# OpenEEW_sensor_board_-_ethernet.net
KiCad netlist of a schematic drawn in EAGLE
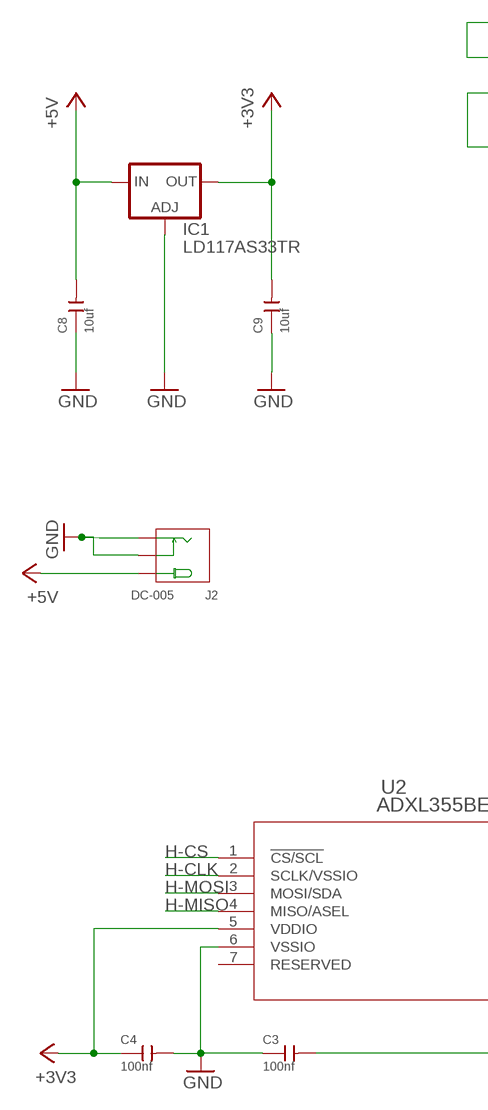
[diagram p0: schematic, sheet 1, part 1 of 2]
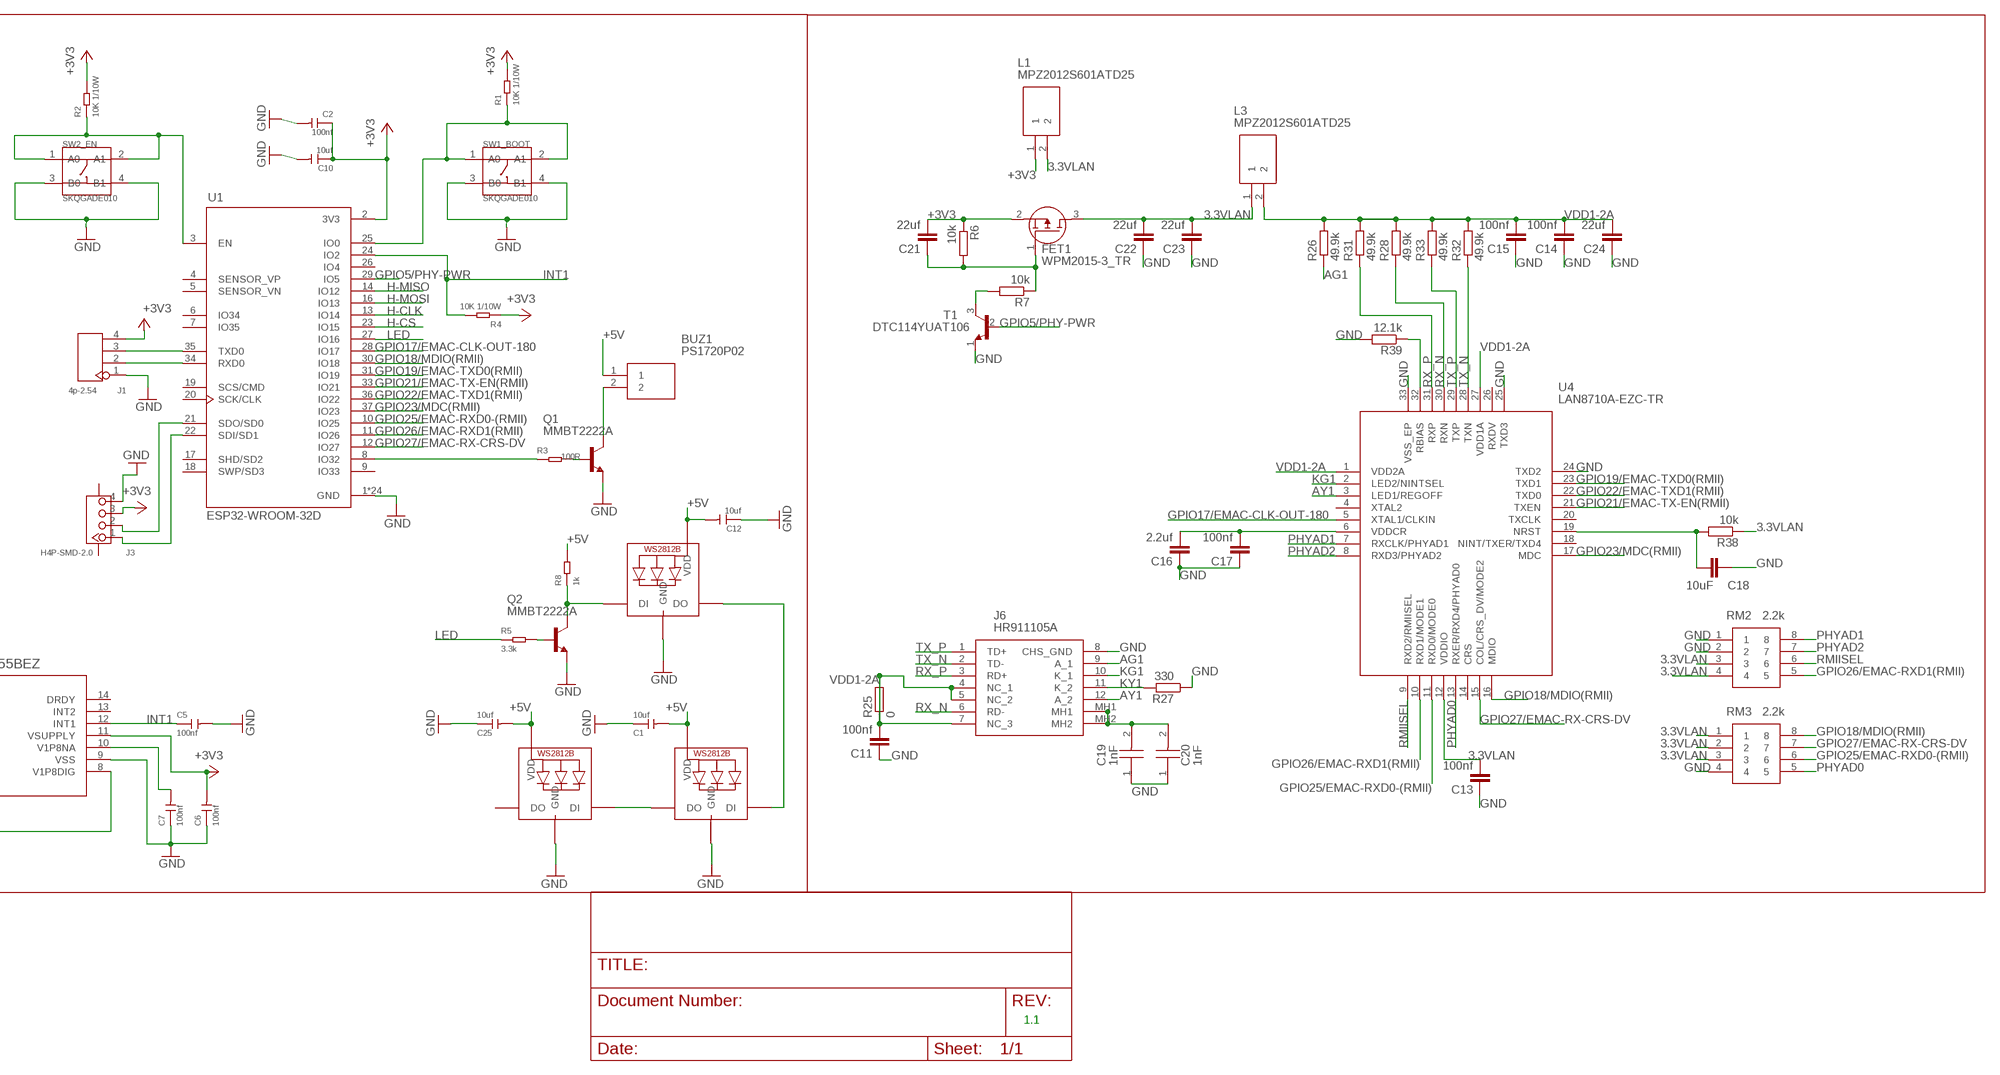
[diagram p1: schematic, sheet 1, part 2 of 2]

(export (version "E")
  (design (tool "Eeschema 10.0.6"))
  (components
    (comp (ref "BUZ1")
      (value "PS1720P02")
      (footprint "eagle-import:PS17_1")
      (fields (field (name "MOUSER_PART_NUMBER") "810-PS1720P02"))
      (libsource (lib "eagle-import") (part "PS1720P02"))
    )
    (comp (ref "C1")
      (value "10uf")
      (footprint "eagle-import:C0603")
      (fields (field (name "MPN") "CC0603KRX5R6BB106"))
      (libsource (lib "eagle-import") (part "CERAMIC-10UF-10V-10%-X5R(0603)"))
    )
    (comp (ref "C2")
      (value "100nf")
      (footprint "eagle-import:C0603")
      (fields (field (name "MPN") "CC0603KRX7R9BB104"))
      (libsource (lib "eagle-import") (part "CERAMIC-100NF-50V-10%-X7R(0603)"))
    )
    (comp (ref "C3")
      (value "100nf")
      (footprint "eagle-import:C0603")
      (fields (field (name "MPN") "CC0603KRX7R9BB104"))
      (libsource (lib "eagle-import") (part "CERAMIC-100NF-50V-10%-X7R(0603)"))
    )
    (comp (ref "C4")
      (value "100nf")
      (footprint "eagle-import:C0603")
      (fields (field (name "MPN") "CC0603KRX7R9BB104"))
      (libsource (lib "eagle-import") (part "CERAMIC-100NF-50V-10%-X7R(0603)"))
    )
    (comp (ref "C5")
      (value "100nf")
      (footprint "eagle-import:C0603")
      (fields (field (name "MPN") "CC0603KRX7R9BB104"))
      (libsource (lib "eagle-import") (part "CERAMIC-100NF-50V-10%-X7R(0603)"))
    )
    (comp (ref "C6")
      (value "100nf")
      (footprint "eagle-import:C0603")
      (fields (field (name "MPN") "CC0603KRX7R9BB104"))
      (libsource (lib "eagle-import") (part "CERAMIC-100NF-50V-10%-X7R(0603)"))
    )
    (comp (ref "C7")
      (value "100nf")
      (footprint "eagle-import:C0603")
      (fields (field (name "MPN") "CC0603KRX7R9BB104"))
      (libsource (lib "eagle-import") (part "CERAMIC-100NF-50V-10%-X7R(0603)"))
    )
    (comp (ref "C8")
      (value "10uf")
      (footprint "eagle-import:C0603")
      (fields (field (name "MPN") "CC0603KRX5R6BB106"))
      (libsource (lib "eagle-import") (part "CERAMIC-10UF-10V-10%-X5R(0603)"))
    )
    (comp (ref "C9")
      (value "10uf")
      (footprint "eagle-import:C0603")
      (fields (field (name "MPN") "CC0603KRX5R6BB106"))
      (libsource (lib "eagle-import") (part "CERAMIC-10UF-10V-10%-X5R(0603)"))
    )
    (comp (ref "C10")
      (value "10uf")
      (footprint "eagle-import:C0603")
      (fields (field (name "MPN") "CC0603KRX5R6BB106"))
      (libsource (lib "eagle-import") (part "CERAMIC-10UF-10V-10%-X5R(0603)"))
    )
    (comp (ref "C11")
      (value "100nf")
      (footprint "eagle-import:C0603")
      (libsource (lib "eagle-import") (part "C-EUC0603"))
    )
    (comp (ref "C12")
      (value "10uf")
      (footprint "eagle-import:C0603")
      (fields (field (name "MPN") "CC0603KRX5R6BB106"))
      (libsource (lib "eagle-import") (part "CERAMIC-10UF-10V-10%-X5R(0603)"))
    )
    (comp (ref "C13")
      (value "100nf")
      (footprint "eagle-import:C0603")
      (libsource (lib "eagle-import") (part "C-EUC0603"))
    )
    (comp (ref "C14")
      (value "100nf")
      (footprint "eagle-import:C0603")
      (libsource (lib "eagle-import") (part "C-EUC0603"))
    )
    (comp (ref "C15")
      (value "100nf")
      (footprint "eagle-import:C0603")
      (libsource (lib "eagle-import") (part "C-EUC0603"))
    )
    (comp (ref "C16")
      (value "2.2uf")
      (footprint "eagle-import:C0603")
      (libsource (lib "eagle-import") (part "C-EUC0603"))
    )
    (comp (ref "C17")
      (value "100nf")
      (footprint "eagle-import:C0603")
      (libsource (lib "eagle-import") (part "C-EUC0603"))
    )
    (comp (ref "C18")
      (value "10uF")
      (footprint "eagle-import:C0603")
      (libsource (lib "eagle-import") (part "C-EUC0603"))
    )
    (comp (ref "C19")
      (value "1nF")
      (footprint "eagle-import:CAPC3317X180N")
      (fields
        (field (name "ARROW_PART_NUMBER") "1206GC102KAT1A")
        (field (name "MOUSER_PART_NUMBER") "581-1206GC102K")
      )
      (libsource (lib "eagle-import") (part "1206GC102KAT1A"))
    )
    (comp (ref "C20")
      (value "1nF")
      (footprint "eagle-import:CAPC3317X180N")
      (fields
        (field (name "ARROW_PART_NUMBER") "1206GC102KAT1A")
        (field (name "MOUSER_PART_NUMBER") "581-1206GC102K")
      )
      (libsource (lib "eagle-import") (part "1206GC102KAT1A"))
    )
    (comp (ref "C21")
      (value "22uf")
      (footprint "eagle-import:C0805")
      (libsource (lib "eagle-import") (part "C-EUC0805"))
    )
    (comp (ref "C22")
      (value "22uf")
      (footprint "eagle-import:C0805")
      (libsource (lib "eagle-import") (part "C-EUC0805"))
    )
    (comp (ref "C23")
      (value "22uf")
      (footprint "eagle-import:C0805")
      (libsource (lib "eagle-import") (part "C-EUC0805"))
    )
    (comp (ref "C24")
      (value "22uf")
      (footprint "eagle-import:C0603")
      (libsource (lib "eagle-import") (part "C-EUC0603"))
    )
    (comp (ref "C25")
      (value "10uf")
      (footprint "eagle-import:C0603")
      (fields (field (name "MPN") "CC0603KRX5R6BB106"))
      (libsource (lib "eagle-import") (part "CERAMIC-10UF-10V-10%-X5R(0603)"))
    )
    (comp (ref "FET1")
      (value "WPM2015-3_TR")
      (footprint "eagle-import:SOT95P240X130-3N")
      (fields (field (name "ARROW_PART_NUMBER") "WPM2015-3/TR"))
      (libsource (lib "eagle-import") (part "WPM2015-3_TR"))
    )
    (comp (ref "IC1")
      (value "LD117AS33TR")
      (footprint "eagle-import:SOT223")
      (libsource (lib "eagle-import") (part "LD117A?S33TR"))
    )
    (comp (ref "J1")
      (value "4p-2.54")
      (footprint "eagle-import:H4-2.54")
      (fields (field (name "MPN") "P125-1104A0BS116A1"))
      (libsource (lib "eagle-import") (part "DIP-BLACK-MALE-HEADER-VERT(4P-2.54)"))
    )
    (comp (ref "J2")
      (value "DC-005")
      (footprint "eagle-import:DCJ3P-14.2X11.0X9.0MM")
      (libsource (lib "eagle-import") (part "CONN-POWER-JACK-2.1MM(DC-005)"))
    )
    (comp (ref "J3")
      (value "H4P-SMD-2.0")
      (footprint "eagle-import:HW4-SMD-2.0")
      (libsource (lib "eagle-import") (part "GROVE-CONNECTOR-SMD(4+2P-2.0)"))
    )
    (comp (ref "J6")
      (value "HR911105A")
      (footprint "eagle-import:HR911105A")
      (libsource (lib "eagle-import") (part "HR911105A"))
    )
    (comp (ref "L1")
      (value "MPZ2012S601ATD25")
      (footprint "eagle-import:BEADC2012X105N")
      (fields (field (name "MOUSER_PART_NUMBER") "810-MPZ2012S601ATD25"))
      (libsource (lib "eagle-import") (part "MPZ2012S601ATD25"))
    )
    (comp (ref "L3")
      (value "MPZ2012S601ATD25")
      (footprint "eagle-import:BEADC2012X105N")
      (fields (field (name "MOUSER_PART_NUMBER") "810-MPZ2012S601ATD25"))
      (libsource (lib "eagle-import") (part "MPZ2012S601ATD25"))
    )
    (comp (ref "LED1")
      (value "WS2812B5050")
      (footprint "eagle-import:WS2812B")
      (libsource (lib "eagle-import") (part "WS2812B5050"))
    )
    (comp (ref "LED2")
      (value "WS2812B5050")
      (footprint "eagle-import:WS2812B")
      (libsource (lib "eagle-import") (part "WS2812B5050"))
    )
    (comp (ref "LED3")
      (value "WS2812B5050")
      (footprint "eagle-import:WS2812B")
      (libsource (lib "eagle-import") (part "WS2812B5050"))
    )
    (comp (ref "Q1")
      (value "MMBT2222A")
      (footprint "eagle-import:SOT23")
      (fields (field (name "MF") "STMicroelectronics"))
      (libsource (lib "eagle-import") (part "MMBT2222A"))
    )
    (comp (ref "Q2")
      (value "MMBT2222A")
      (footprint "eagle-import:SOT23")
      (fields (field (name "MF") "STMicroelectronics"))
      (libsource (lib "eagle-import") (part "MMBT2222A"))
    )
    (comp (ref "R1")
      (value "10K 1/10W")
      (footprint "eagle-import:R0603")
      (fields (field (name "MPN") "RC0603JR-0710KL"))
      (libsource (lib "eagle-import") (part "SMD-RES-10K-5%-1/10W(0603)"))
    )
    (comp (ref "R2")
      (value "10K 1/10W")
      (footprint "eagle-import:R0603")
      (fields (field (name "MPN") "RC0603JR-0710KL"))
      (libsource (lib "eagle-import") (part "SMD-RES-10K-5%-1/10W(0603)"))
    )
    (comp (ref "R3")
      (value "100R")
      (footprint "eagle-import:R0805")
      (fields (field (name "MPN") "RC0805JR-07100RL"))
      (libsource (lib "eagle-import") (part "SMD-RES-100R-5%-1/8W(0805)"))
    )
    (comp (ref "R4")
      (value "10K 1/10W")
      (footprint "eagle-import:R0603")
      (fields (field (name "MPN") "RC0603JR-0710KL"))
      (libsource (lib "eagle-import") (part "SMD-RES-10K-5%-1/10W(0603)"))
    )
    (comp (ref "R5")
      (value "3.3k")
      (footprint "eagle-import:R0603")
      (fields (field (name "MPN") "RC0603FR-071K5L"))
      (libsource (lib "eagle-import") (part "SMD-RES-300R-1%-1/10W(0603)"))
    )
    (comp (ref "R6")
      (value "10k")
      (footprint "eagle-import:R0603")
      (libsource (lib "eagle-import") (part "R-EU_R0603"))
    )
    (comp (ref "R7")
      (value "10k")
      (footprint "eagle-import:R0603")
      (libsource (lib "eagle-import") (part "R-EU_R0603"))
    )
    (comp (ref "R8")
      (value "1k")
      (footprint "eagle-import:R0805")
      (fields (field (name "MPN") "RC0805JR-07100RL"))
      (libsource (lib "eagle-import") (part "SMD-RES-100R-5%-1/8W(0805)"))
    )
    (comp (ref "R25")
      (value "0")
      (footprint "eagle-import:R0603")
      (libsource (lib "eagle-import") (part "R-EU_R0603"))
    )
    (comp (ref "R26")
      (value "49.9k")
      (footprint "eagle-import:R0603")
      (libsource (lib "eagle-import") (part "R-EU_R0603"))
    )
    (comp (ref "R27")
      (value "330")
      (footprint "eagle-import:R0603")
      (libsource (lib "eagle-import") (part "R-EU_R0603"))
    )
    (comp (ref "R28")
      (value "49.9k")
      (footprint "eagle-import:R0603")
      (libsource (lib "eagle-import") (part "R-EU_R0603"))
    )
    (comp (ref "R31")
      (value "49.9k")
      (footprint "eagle-import:R0603")
      (libsource (lib "eagle-import") (part "R-EU_R0603"))
    )
    (comp (ref "R32")
      (value "49.9k")
      (footprint "eagle-import:R0603")
      (libsource (lib "eagle-import") (part "R-EU_R0603"))
    )
    (comp (ref "R33")
      (value "49.9k")
      (footprint "eagle-import:R0603")
      (libsource (lib "eagle-import") (part "R-EU_R0603"))
    )
    (comp (ref "R38")
      (value "10k")
      (footprint "eagle-import:R0603")
      (libsource (lib "eagle-import") (part "R-EU_R0603"))
    )
    (comp (ref "R39")
      (value "12.1k")
      (footprint "eagle-import:R0603")
      (libsource (lib "eagle-import") (part "R-EU_R0603"))
    )
    (comp (ref "RM2")
      (value "2.2k")
      (footprint "eagle-import:CAT10J4LF")
      (fields
        (field (name "ARROW_PART_NUMBER") "CAT10-103J4LF")
        (field (name "MOUSER_PART_NUMBER") "652-CAT10-103J4LF")
      )
      (libsource (lib "eagle-import") (part "CAT10-103J4LF"))
    )
    (comp (ref "RM3")
      (value "2.2k")
      (footprint "eagle-import:CAT10J4LF")
      (fields
        (field (name "ARROW_PART_NUMBER") "CAT10-103J4LF")
        (field (name "MOUSER_PART_NUMBER") "652-CAT10-103J4LF")
      )
      (libsource (lib "eagle-import") (part "CAT10-103J4LF"))
    )
    (comp (ref "SW1_BOOT")
      (value "SKQGADE010")
      (footprint "eagle-import:SW4-SMD-5.2X5.2X1.5MM")
      (libsource (lib "eagle-import") (part "SMD-BUTTON(4P-5.2X5.2X1.5MM-SKQGADE010)-SKQGADE010"))
    )
    (comp (ref "SW2_EN")
      (value "SKQGADE010")
      (footprint "eagle-import:SW4-SMD-5.2X5.2X1.5MM")
      (libsource (lib "eagle-import") (part "SMD-BUTTON(4P-5.2X5.2X1.5MM-SKQGADE010)-SKQGADE010"))
    )
    (comp (ref "T1")
      (value "DTC114YUAT106")
      (footprint "eagle-import:SOT65P210X90-3N")
      (fields (field (name "MOUSER_PART_NUMBER") "755-DTC114YUAT106"))
      (libsource (lib "eagle-import") (part "DTC114YUAT106"))
    )
    (comp (ref "U1")
      (value "ESP32-WROOM-32D")
      (footprint "eagle-import:MODULE_ESP32-WROOM-32D")
      (fields (field (name "MF") "Espressif Systems"))
      (libsource (lib "eagle-import") (part "ESP32-WROOM-32D"))
    )
    (comp (ref "U2")
      (value "ADXL355BEZ")
      (footprint "eagle-import:E_14_1_ADI")
      (fields (field (name "COPYRIGHT") "Copyright (C) 2018 Accelerated Designs. All rights reserved"))
      (libsource (lib "eagle-import") (part "ADXL355BEZ"))
    )
    (comp (ref "U4")
      (value "LAN8710A-EZC-TR")
      (footprint "eagle-import:QFN50P500X500X100-33N")
      (fields (field (name "MOUSER_PART_NUMBER") "886-LAN8710A-EZC-TR"))
      (libsource (lib "eagle-import") (part "LAN8710A-EZC-TR"))
    )
  )
  (nets
    (net (code "1") (name "+3V3") (class "Default")
      (node (ref "C10") (pin "1") (pinfunction "1_1") (pintype "passive"))
      (node (ref "C2") (pin "1") (pinfunction "1_1") (pintype "passive"))
      (node (ref "C21") (pin "2") (pinfunction "2_2") (pintype "passive"))
      (node (ref "C4") (pin "1") (pinfunction "1_1") (pintype "passive"))
      (node (ref "C6") (pin "2") (pinfunction "2_2") (pintype "passive"))
      (node (ref "C9") (pin "2") (pinfunction "2_2") (pintype "passive"))
      (node (ref "FET1") (pin "2") (pinfunction "S_2") (pintype "bidirectional"))
      (node (ref "IC1") (pin "4") (pinfunction "OUT_4") (pintype "passive"))
      (node (ref "J1") (pin "4") (pinfunction "P$4_4") (pintype "bidirectional"))
      (node (ref "J3") (pin "3") (pinfunction "3_3") (pintype "bidirectional"))
      (node (ref "L1") (pin "1") (pinfunction "1_1") (pintype "bidirectional"))
      (node (ref "R1") (pin "2") (pinfunction "2_2") (pintype "passive"))
      (node (ref "R2") (pin "2") (pinfunction "2_2") (pintype "passive"))
      (node (ref "R4") (pin "1") (pinfunction "1_1") (pintype "passive"))
      (node (ref "R6") (pin "1") (pinfunction "1_1") (pintype "passive"))
      (node (ref "U1") (pin "2") (pinfunction "3V3_2") (pintype "power_in"))
      (node (ref "U2") (pin "11") (pinfunction "VSUPPLY_11") (pintype "passive"))
      (node (ref "U2") (pin "5") (pinfunction "VDDIO_5") (pintype "passive"))
    )
    (net (code "2") (name "+5V") (class "Default")
      (node (ref "BUZ1") (pin "1") (pinfunction "1_1") (pintype "bidirectional"))
      (node (ref "C1") (pin "2") (pinfunction "2_2") (pintype "passive"))
      (node (ref "C12") (pin "2") (pinfunction "2_2") (pintype "passive"))
      (node (ref "C25") (pin "2") (pinfunction "2_2") (pintype "passive"))
      (node (ref "C8") (pin "2") (pinfunction "2_2") (pintype "passive"))
      (node (ref "IC1") (pin "3") (pinfunction "IN_3") (pintype "input"))
      (node (ref "J2") (pin "+") (pinfunction "+_+") (pintype "bidirectional"))
      (node (ref "LED1") (pin "1-VDD") (pinfunction "VDD_1-VDD") (pintype "power_in"))
      (node (ref "LED2") (pin "1-VDD") (pinfunction "VDD_1-VDD") (pintype "power_in"))
      (node (ref "LED3") (pin "1-VDD") (pinfunction "VDD_1-VDD") (pintype "power_in"))
      (node (ref "R8") (pin "2") (pinfunction "2_2") (pintype "passive"))
    )
    (net (code "3") (name "/3.3VLAN") (class "Default")
      (node (ref "C13") (pin "2") (pinfunction "2_2") (pintype "passive"))
      (node (ref "C22") (pin "2") (pinfunction "2_2") (pintype "passive"))
      (node (ref "C23") (pin "2") (pinfunction "2_2") (pintype "passive"))
      (node (ref "FET1") (pin "3") (pinfunction "D_3") (pintype "bidirectional"))
      (node (ref "L1") (pin "2") (pinfunction "2_2") (pintype "bidirectional"))
      (node (ref "L3") (pin "1") (pinfunction "1_1") (pintype "bidirectional"))
      (node (ref "R38") (pin "1") (pinfunction "1_1") (pintype "passive"))
      (node (ref "RM2") (pin "3") (pinfunction "3_3") (pintype "bidirectional"))
      (node (ref "RM2") (pin "4") (pinfunction "4_4") (pintype "bidirectional"))
      (node (ref "RM3") (pin "1") (pinfunction "1_1") (pintype "bidirectional"))
      (node (ref "RM3") (pin "2") (pinfunction "2_2") (pintype "bidirectional"))
      (node (ref "RM3") (pin "3") (pinfunction "3_3") (pintype "bidirectional"))
      (node (ref "U4") (pin "12") (pinfunction "VDDIO_12") (pintype "power_in"))
    )
    (net (code "4") (name "/AG1") (class "Default")
      (node (ref "J6") (pin "9") (pinfunction "A_1_9") (pintype "bidirectional"))
      (node (ref "R26") (pin "1") (pinfunction "1_1") (pintype "passive"))
    )
    (net (code "5") (name "/AY1") (class "Default")
      (node (ref "J6") (pin "12") (pinfunction "A_2_12") (pintype "bidirectional"))
      (node (ref "U4") (pin "3") (pinfunction "LED1/REGOFF_3") (pintype "bidirectional"))
    )
    (net (code "6") (name "/GPIO5{slash}PHY-PWR") (class "Default")
      (node (ref "T1") (pin "2") (pinfunction "B_2") (pintype "input"))
      (node (ref "U1") (pin "29") (pinfunction "IO5_29") (pintype "bidirectional"))
    )
    (net (code "7") (name "/GPIO17{slash}EMAC-CLK-OUT-180") (class "Default")
      (node (ref "U1") (pin "28") (pinfunction "IO17_28") (pintype "bidirectional"))
      (node (ref "U4") (pin "5") (pinfunction "XTAL1/CLKIN_5") (pintype "input"))
    )
    (net (code "8") (name "/GPIO18{slash}MDIO(RMII)") (class "Default")
      (node (ref "RM3") (pin "8") (pinfunction "8_8") (pintype "bidirectional"))
      (node (ref "U1") (pin "30") (pinfunction "IO18_30") (pintype "bidirectional"))
      (node (ref "U4") (pin "16") (pinfunction "MDIO_16") (pintype "bidirectional"))
    )
    (net (code "9") (name "/GPIO19{slash}EMAC-TXD0(RMII)") (class "Default")
      (node (ref "U1") (pin "31") (pinfunction "IO19_31") (pintype "bidirectional"))
      (node (ref "U4") (pin "23") (pinfunction "TXD1_23") (pintype "bidirectional"))
    )
    (net (code "10") (name "/GPIO21{slash}EMAC-TX-EN(RMII)") (class "Default")
      (node (ref "U1") (pin "33") (pinfunction "IO21_33") (pintype "bidirectional"))
      (node (ref "U4") (pin "21") (pinfunction "TXEN_21") (pintype "bidirectional"))
    )
    (net (code "11") (name "/GPIO22{slash}EMAC-TXD1(RMII)") (class "Default")
      (node (ref "U1") (pin "36") (pinfunction "IO22_36") (pintype "bidirectional"))
      (node (ref "U4") (pin "22") (pinfunction "TXD0_22") (pintype "bidirectional"))
    )
    (net (code "12") (name "/GPIO23{slash}MDC(RMII)") (class "Default")
      (node (ref "U1") (pin "37") (pinfunction "IO23_37") (pintype "bidirectional"))
      (node (ref "U4") (pin "17") (pinfunction "MDC_17") (pintype "bidirectional"))
    )
    (net (code "13") (name "/GPIO25{slash}EMAC-RXD0-(RMII)") (class "Default")
      (node (ref "RM3") (pin "6") (pinfunction "6_6") (pintype "bidirectional"))
      (node (ref "U1") (pin "10") (pinfunction "IO25_10") (pintype "bidirectional"))
      (node (ref "U4") (pin "11") (pinfunction "RXD0/MODE0_11") (pintype "bidirectional"))
    )
    (net (code "14") (name "/GPIO26{slash}EMAC-RXD1(RMII)") (class "Default")
      (node (ref "RM2") (pin "5") (pinfunction "5_5") (pintype "bidirectional"))
      (node (ref "U1") (pin "11") (pinfunction "IO26_11") (pintype "bidirectional"))
      (node (ref "U4") (pin "10") (pinfunction "RXD1/MODE1_10") (pintype "bidirectional"))
    )
    (net (code "15") (name "/GPIO27{slash}EMAC-RX-CRS-DV") (class "Default")
      (node (ref "RM3") (pin "7") (pinfunction "7_7") (pintype "bidirectional"))
      (node (ref "U1") (pin "12") (pinfunction "IO27_12") (pintype "bidirectional"))
      (node (ref "U4") (pin "15") (pinfunction "COL/CRS_DV/MODE2_15") (pintype "bidirectional"))
    )
    (net (code "16") (name "/H-CLK") (class "Default")
      (node (ref "U1") (pin "13") (pinfunction "IO14_13") (pintype "bidirectional"))
      (node (ref "U2") (pin "2") (pinfunction "SCLK/VSSIO_2") (pintype "passive"))
    )
    (net (code "17") (name "/H-CS") (class "Default")
      (node (ref "U1") (pin "23") (pinfunction "IO15_23") (pintype "bidirectional"))
      (node (ref "U2") (pin "1") (pinfunction "~{CS/SCL}_1") (pintype "passive"))
    )
    (net (code "18") (name "/H-MISO") (class "Default")
      (node (ref "U1") (pin "14") (pinfunction "IO12_14") (pintype "bidirectional"))
      (node (ref "U2") (pin "4") (pinfunction "MISO/ASEL_4") (pintype "passive"))
    )
    (net (code "19") (name "/H-MOSI") (class "Default")
      (node (ref "U1") (pin "16") (pinfunction "IO13_16") (pintype "bidirectional"))
      (node (ref "U2") (pin "3") (pinfunction "MOSI/SDA_3") (pintype "passive"))
    )
    (net (code "20") (name "/INT1") (class "Default")
      (node (ref "C5") (pin "1") (pinfunction "1_1") (pintype "passive"))
      (node (ref "R4") (pin "2") (pinfunction "2_2") (pintype "passive"))
      (node (ref "U1") (pin "24") (pinfunction "IO2_24") (pintype "bidirectional"))
      (node (ref "U2") (pin "12") (pinfunction "INT1_12") (pintype "passive"))
    )
    (net (code "21") (name "/KG1") (class "Default")
      (node (ref "J6") (pin "10") (pinfunction "K_1_10") (pintype "bidirectional"))
      (node (ref "U4") (pin "2") (pinfunction "LED2/NINTSEL_2") (pintype "input"))
    )
    (net (code "22") (name "/KY1") (class "Default")
      (node (ref "J6") (pin "11") (pinfunction "K_2_11") (pintype "bidirectional"))
      (node (ref "R27") (pin "2") (pinfunction "2_2") (pintype "passive"))
    )
    (net (code "23") (name "/LED") (class "Default")
      (node (ref "R5") (pin "1") (pinfunction "1_1") (pintype "passive"))
      (node (ref "U1") (pin "27") (pinfunction "IO16_27") (pintype "bidirectional"))
    )
    (net (code "24") (name "/PHYAD0") (class "Default")
      (node (ref "RM3") (pin "5") (pinfunction "5_5") (pintype "bidirectional"))
      (node (ref "U4") (pin "13") (pinfunction "RXER/RXD4/PHYAD0_13") (pintype "bidirectional"))
    )
    (net (code "25") (name "/PHYAD1") (class "Default")
      (node (ref "RM2") (pin "8") (pinfunction "8_8") (pintype "bidirectional"))
      (node (ref "U4") (pin "7") (pinfunction "RXCLK/PHYAD1_7") (pintype "input"))
    )
    (net (code "26") (name "/PHYAD2") (class "Default")
      (node (ref "RM2") (pin "7") (pinfunction "7_7") (pintype "bidirectional"))
      (node (ref "U4") (pin "8") (pinfunction "RXD3/PHYAD2_8") (pintype "bidirectional"))
    )
    (net (code "27") (name "/RMIISEL") (class "Default")
      (node (ref "RM2") (pin "6") (pinfunction "6_6") (pintype "bidirectional"))
      (node (ref "U4") (pin "9") (pinfunction "RXD2/RMIISEL_9") (pintype "bidirectional"))
    )
    (net (code "28") (name "/RX_N") (class "Default")
      (node (ref "J6") (pin "6") (pinfunction "RD-_6") (pintype "bidirectional"))
      (node (ref "R28") (pin "1") (pinfunction "1_1") (pintype "passive"))
      (node (ref "U4") (pin "30") (pinfunction "RXN_30") (pintype "bidirectional"))
    )
    (net (code "29") (name "/RX_P") (class "Default")
      (node (ref "J6") (pin "3") (pinfunction "RD+_3") (pintype "bidirectional"))
      (node (ref "R31") (pin "1") (pinfunction "1_1") (pintype "passive"))
      (node (ref "U4") (pin "31") (pinfunction "RXP_31") (pintype "bidirectional"))
    )
    (net (code "30") (name "/TX_N") (class "Default")
      (node (ref "J6") (pin "2") (pinfunction "TD-_2") (pintype "bidirectional"))
      (node (ref "R32") (pin "1") (pinfunction "1_1") (pintype "passive"))
      (node (ref "U4") (pin "28") (pinfunction "TXN_28") (pintype "bidirectional"))
    )
    (net (code "31") (name "/TX_P") (class "Default")
      (node (ref "J6") (pin "1") (pinfunction "TD+_1") (pintype "bidirectional"))
      (node (ref "R33") (pin "1") (pinfunction "1_1") (pintype "passive"))
      (node (ref "U4") (pin "29") (pinfunction "TXP_29") (pintype "bidirectional"))
    )
    (net (code "32") (name "/VDD1-2A") (class "Default")
      (node (ref "C11") (pin "2") (pinfunction "2_2") (pintype "passive"))
      (node (ref "C14") (pin "2") (pinfunction "2_2") (pintype "passive"))
      (node (ref "C15") (pin "2") (pinfunction "2_2") (pintype "passive"))
      (node (ref "C24") (pin "2") (pinfunction "2_2") (pintype "passive"))
      (node (ref "J6") (pin "4") (pinfunction "NC_1_4") (pintype "bidirectional"))
      (node (ref "J6") (pin "5") (pinfunction "NC_2_5") (pintype "bidirectional"))
      (node (ref "J6") (pin "7") (pinfunction "NC_3_7") (pintype "bidirectional"))
      (node (ref "L3") (pin "2") (pinfunction "2_2") (pintype "bidirectional"))
      (node (ref "R25") (pin "1") (pinfunction "1_1") (pintype "passive"))
      (node (ref "R25") (pin "2") (pinfunction "2_2") (pintype "passive"))
      (node (ref "R26") (pin "2") (pinfunction "2_2") (pintype "passive"))
      (node (ref "R28") (pin "2") (pinfunction "2_2") (pintype "passive"))
      (node (ref "R31") (pin "2") (pinfunction "2_2") (pintype "passive"))
      (node (ref "R32") (pin "2") (pinfunction "2_2") (pintype "passive"))
      (node (ref "R33") (pin "2") (pinfunction "2_2") (pintype "passive"))
      (node (ref "U4") (pin "1") (pinfunction "VDD2A_1") (pintype "power_in"))
      (node (ref "U4") (pin "27") (pinfunction "VDD1A_27") (pintype "power_in"))
    )
    (net (code "33") (name "GND") (class "Default")
      (node (ref "C1") (pin "1") (pinfunction "1_1") (pintype "passive"))
      (node (ref "C10") (pin "2") (pinfunction "2_2") (pintype "passive"))
      (node (ref "C11") (pin "1") (pinfunction "1_1") (pintype "passive"))
      (node (ref "C12") (pin "1") (pinfunction "1_1") (pintype "passive"))
      (node (ref "C13") (pin "1") (pinfunction "1_1") (pintype "passive"))
      (node (ref "C14") (pin "1") (pinfunction "1_1") (pintype "passive"))
      (node (ref "C15") (pin "1") (pinfunction "1_1") (pintype "passive"))
      (node (ref "C16") (pin "1") (pinfunction "1_1") (pintype "passive"))
      (node (ref "C17") (pin "1") (pinfunction "1_1") (pintype "passive"))
      (node (ref "C18") (pin "1") (pinfunction "1_1") (pintype "passive"))
      (node (ref "C19") (pin "1") (pinfunction "1_1") (pintype "bidirectional"))
      (node (ref "C2") (pin "2") (pinfunction "2_2") (pintype "passive"))
      (node (ref "C20") (pin "1") (pinfunction "1_1") (pintype "bidirectional"))
      (node (ref "C22") (pin "1") (pinfunction "1_1") (pintype "passive"))
      (node (ref "C23") (pin "1") (pinfunction "1_1") (pintype "passive"))
      (node (ref "C24") (pin "1") (pinfunction "1_1") (pintype "passive"))
      (node (ref "C25") (pin "1") (pinfunction "1_1") (pintype "passive"))
      (node (ref "C3") (pin "1") (pinfunction "1_1") (pintype "passive"))
      (node (ref "C4") (pin "2") (pinfunction "2_2") (pintype "passive"))
      (node (ref "C5") (pin "2") (pinfunction "2_2") (pintype "passive"))
      (node (ref "C6") (pin "1") (pinfunction "1_1") (pintype "passive"))
      (node (ref "C7") (pin "1") (pinfunction "1_1") (pintype "passive"))
      (node (ref "C8") (pin "1") (pinfunction "1_1") (pintype "passive"))
      (node (ref "C9") (pin "1") (pinfunction "1_1") (pintype "passive"))
      (node (ref "IC1") (pin "1") (pinfunction "ADJ_1") (pintype "input"))
      (node (ref "J1") (pin "1") (pinfunction "P$1_1") (pintype "bidirectional"))
      (node (ref "J2") (pin "-1") (pinfunction "-_-1") (pintype "bidirectional"))
      (node (ref "J2") (pin "-2") (pinfunction "CDN_-2") (pintype "bidirectional"))
      (node (ref "J3") (pin "4") (pinfunction "4_4") (pintype "bidirectional"))
      (node (ref "J6") (pin "8") (pinfunction "CHS_GND_8") (pintype "bidirectional"))
      (node (ref "LED1") (pin "3-GND") (pinfunction "GND_3-GND") (pintype "power_in"))
      (node (ref "LED2") (pin "3-GND") (pinfunction "GND_3-GND") (pintype "power_in"))
      (node (ref "LED3") (pin "3-GND") (pinfunction "GND_3-GND") (pintype "power_in"))
      (node (ref "Q1") (pin "2") (pinfunction "E_2") (pintype "passive"))
      (node (ref "Q2") (pin "2") (pinfunction "E_2") (pintype "passive"))
      (node (ref "R27") (pin "1") (pinfunction "1_1") (pintype "passive"))
      (node (ref "R39") (pin "2") (pinfunction "2_2") (pintype "passive"))
      (node (ref "RM2") (pin "1") (pinfunction "1_1") (pintype "bidirectional"))
      (node (ref "RM2") (pin "2") (pinfunction "2_2") (pintype "bidirectional"))
      (node (ref "RM3") (pin "4") (pinfunction "4_4") (pintype "bidirectional"))
      (node (ref "SW1_BOOT") (pin "3") (pinfunction "B0_3") (pintype "bidirectional"))
      (node (ref "SW1_BOOT") (pin "4") (pinfunction "B1_4") (pintype "bidirectional"))
      (node (ref "SW2_EN") (pin "3") (pinfunction "B0_3") (pintype "bidirectional"))
      (node (ref "SW2_EN") (pin "4") (pinfunction "B1_4") (pintype "bidirectional"))
      (node (ref "T1") (pin "1") (pinfunction "E_1") (pintype "power_in"))
      (node (ref "U1") (pin "1") (pinfunction "GND_1") (pintype "power_in"))
      (node (ref "U1") (pin "15") (pinfunction "GND_15") (pintype "power_in"))
      (node (ref "U1") (pin "38") (pinfunction "GND_38") (pintype "power_in"))
      (node (ref "U1") (pin "39_1") (pinfunction "GND_39_1") (pintype "power_in"))
      (node (ref "U1") (pin "39_10") (pinfunction "GND_39_10") (pintype "power_in"))
      (node (ref "U1") (pin "39_11") (pinfunction "GND_39_11") (pintype "power_in"))
      (node (ref "U1") (pin "39_12") (pinfunction "GND_39_12") (pintype "power_in"))
      (node (ref "U1") (pin "39_13") (pinfunction "GND_39_13") (pintype "power_in"))
      (node (ref "U1") (pin "39_14") (pinfunction "GND_39_14") (pintype "power_in"))
      (node (ref "U1") (pin "39_15") (pinfunction "GND_39_15") (pintype "power_in"))
      (node (ref "U1") (pin "39_16") (pinfunction "GND_39_16") (pintype "power_in"))
      (node (ref "U1") (pin "39_17") (pinfunction "GND_39_17") (pintype "power_in"))
      (node (ref "U1") (pin "39_18") (pinfunction "GND_39_18") (pintype "power_in"))
      (node (ref "U1") (pin "39_19") (pinfunction "GND_39_19") (pintype "power_in"))
      (node (ref "U1") (pin "39_2") (pinfunction "GND_39_2") (pintype "power_in"))
      (node (ref "U1") (pin "39_20") (pinfunction "GND_39_20") (pintype "power_in"))
      (node (ref "U1") (pin "39_21") (pinfunction "GND_39_21") (pintype "power_in"))
      (node (ref "U1") (pin "39_3") (pinfunction "GND_39_3") (pintype "power_in"))
      (node (ref "U1") (pin "39_4") (pinfunction "GND_39_4") (pintype "power_in"))
      (node (ref "U1") (pin "39_5") (pinfunction "GND_39_5") (pintype "power_in"))
      (node (ref "U1") (pin "39_6") (pinfunction "GND_39_6") (pintype "power_in"))
      (node (ref "U1") (pin "39_7") (pinfunction "GND_39_7") (pintype "power_in"))
      (node (ref "U1") (pin "39_8") (pinfunction "GND_39_8") (pintype "power_in"))
      (node (ref "U1") (pin "39_9") (pinfunction "GND_39_9") (pintype "power_in"))
      (node (ref "U2") (pin "6") (pinfunction "VSSIO_6") (pintype "passive"))
      (node (ref "U2") (pin "9") (pinfunction "VSS_9") (pintype "passive"))
      (node (ref "U4") (pin "24") (pinfunction "TXD2_24") (pintype "bidirectional"))
      (node (ref "U4") (pin "25") (pinfunction "TXD3_25") (pintype "bidirectional"))
      (node (ref "U4") (pin "33") (pinfunction "VSS_EP_33") (pintype "power_in"))
    )
    (net (code "34") (name "Net-(C19-Pad2)") (class "Default")
      (node (ref "C19") (pin "2") (pinfunction "2_2") (pintype "bidirectional"))
      (node (ref "C20") (pin "2") (pinfunction "2_2") (pintype "bidirectional"))
      (node (ref "J6") (pin "MH1") (pinfunction "MH1_MH1") (pintype "bidirectional"))
      (node (ref "J6") (pin "MH2") (pinfunction "MH2_MH2") (pintype "bidirectional"))
    )
    (net (code "35") (name "Net-(FET1-G)") (class "Default")
      (node (ref "C21") (pin "1") (pinfunction "1_1") (pintype "passive"))
      (node (ref "FET1") (pin "1") (pinfunction "G_1") (pintype "bidirectional"))
      (node (ref "R6") (pin "2") (pinfunction "2_2") (pintype "passive"))
      (node (ref "R7") (pin "1") (pinfunction "1_1") (pintype "passive"))
    )
    (net (code "36") (name "Net-(J1-P$2)") (class "Default")
      (node (ref "J1") (pin "2") (pinfunction "P$2_2") (pintype "bidirectional"))
      (node (ref "U1") (pin "34") (pinfunction "RXD0_34") (pintype "bidirectional"))
    )
    (net (code "37") (name "Net-(J1-P$3)") (class "Default")
      (node (ref "J1") (pin "3") (pinfunction "P$3_3") (pintype "bidirectional"))
      (node (ref "U1") (pin "35") (pinfunction "TXD0_35") (pintype "bidirectional"))
    )
    (net (code "38") (name "Net-(LED1-DI)") (class "Default")
      (node (ref "LED1") (pin "4-DIN") (pinfunction "DI_4-DIN") (pintype "input"))
      (node (ref "Q2") (pin "3") (pinfunction "C_3") (pintype "passive"))
      (node (ref "R8") (pin "1") (pinfunction "1_1") (pintype "passive"))
    )
    (net (code "39") (name "Net-(LED1-DO)") (class "Default")
      (node (ref "LED1") (pin "2-DOUT") (pinfunction "DO_2-DOUT") (pintype "output"))
      (node (ref "LED2") (pin "4-DIN") (pinfunction "DI_4-DIN") (pintype "input"))
    )
    (net (code "40") (name "Net-(LED2-DO)") (class "Default")
      (node (ref "LED2") (pin "2-DOUT") (pinfunction "DO_2-DOUT") (pintype "output"))
      (node (ref "LED3") (pin "4-DIN") (pinfunction "DI_4-DIN") (pintype "input"))
    )
    (net (code "41") (name "Net-(Q1-B)") (class "Default")
      (node (ref "Q1") (pin "1") (pinfunction "B_1") (pintype "passive"))
      (node (ref "R3") (pin "2") (pinfunction "2_2") (pintype "passive"))
    )
    (net (code "42") (name "Net-(Q1-C)") (class "Default")
      (node (ref "BUZ1") (pin "2") (pinfunction "2_2") (pintype "bidirectional"))
      (node (ref "Q1") (pin "3") (pinfunction "C_3") (pintype "passive"))
    )
    (net (code "43") (name "Net-(Q2-B)") (class "Default")
      (node (ref "Q2") (pin "1") (pinfunction "B_1") (pintype "passive"))
      (node (ref "R5") (pin "2") (pinfunction "2_2") (pintype "passive"))
    )
    (net (code "44") (name "Net-(SW1_BOOT-A0)") (class "Default")
      (node (ref "R1") (pin "1") (pinfunction "1_1") (pintype "passive"))
      (node (ref "SW1_BOOT") (pin "1") (pinfunction "A0_1") (pintype "bidirectional"))
      (node (ref "SW1_BOOT") (pin "2") (pinfunction "A1_2") (pintype "bidirectional"))
      (node (ref "U1") (pin "25") (pinfunction "IO0_25") (pintype "bidirectional"))
    )
    (net (code "45") (name "Net-(SW2_EN-A0)") (class "Default")
      (node (ref "R2") (pin "1") (pinfunction "1_1") (pintype "passive"))
      (node (ref "SW2_EN") (pin "1") (pinfunction "A0_1") (pintype "bidirectional"))
      (node (ref "SW2_EN") (pin "2") (pinfunction "A1_2") (pintype "bidirectional"))
      (node (ref "U1") (pin "3") (pinfunction "EN_3") (pintype "input"))
    )
    (net (code "46") (name "Net-(T1-C)") (class "Default")
      (node (ref "R7") (pin "2") (pinfunction "2_2") (pintype "passive"))
      (node (ref "T1") (pin "3") (pinfunction "C_3") (pintype "output"))
    )
    (net (code "47") (name "Net-(U1-IO32)") (class "Default")
      (node (ref "R3") (pin "1") (pinfunction "1_1") (pintype "passive"))
      (node (ref "U1") (pin "8") (pinfunction "IO32_8") (pintype "bidirectional"))
    )
    (net (code "48") (name "Net-(U1-SDI{slash}SD1)") (class "Default")
      (node (ref "J3") (pin "1") (pinfunction "1_1") (pintype "bidirectional"))
      (node (ref "U1") (pin "22") (pinfunction "SDI/SD1_22") (pintype "bidirectional"))
    )
    (net (code "49") (name "Net-(U1-SDO{slash}SD0)") (class "Default")
      (node (ref "J3") (pin "2") (pinfunction "2_2") (pintype "bidirectional"))
      (node (ref "U1") (pin "21") (pinfunction "SDO/SD0_21") (pintype "bidirectional"))
    )
    (net (code "50") (name "Net-(U2-V1P8DIG)") (class "Default")
      (node (ref "C3") (pin "2") (pinfunction "2_2") (pintype "passive"))
      (node (ref "U2") (pin "8") (pinfunction "V1P8DIG_8") (pintype "passive"))
    )
    (net (code "51") (name "Net-(U2-V1P8NA)") (class "Default")
      (node (ref "C7") (pin "2") (pinfunction "2_2") (pintype "passive"))
      (node (ref "U2") (pin "10") (pinfunction "V1P8NA_10") (pintype "passive"))
    )
    (net (code "52") (name "Net-(U4-NRST)") (class "Default")
      (node (ref "C18") (pin "2") (pinfunction "2_2") (pintype "passive"))
      (node (ref "R38") (pin "2") (pinfunction "2_2") (pintype "passive"))
      (node (ref "U4") (pin "19") (pinfunction "NRST_19") (pintype "input"))
    )
    (net (code "53") (name "Net-(U4-RBIAS)") (class "Default")
      (node (ref "R39") (pin "1") (pinfunction "1_1") (pintype "passive"))
      (node (ref "U4") (pin "32") (pinfunction "RBIAS_32") (pintype "bidirectional"))
    )
    (net (code "54") (name "Net-(U4-VDDCR)") (class "Default")
      (node (ref "C16") (pin "2") (pinfunction "2_2") (pintype "passive"))
      (node (ref "C17") (pin "2") (pinfunction "2_2") (pintype "passive"))
      (node (ref "U4") (pin "6") (pinfunction "VDDCR_6") (pintype "power_in"))
    )
    (net (code "55") (name "unconnected-(J3-PadSS1)") (class "Default")
      (node (ref "J3") (pin "SS1") (pinfunction "SS1_SS1") (pintype "bidirectional"))
    )
    (net (code "56") (name "unconnected-(J3-PadSS2)") (class "Default")
      (node (ref "J3") (pin "SS2") (pinfunction "SS2_SS2") (pintype "bidirectional"))
    )
    (net (code "57") (name "unconnected-(LED3-DO-Pad2-DOUT)") (class "Default")
      (node (ref "LED3") (pin "2-DOUT") (pinfunction "DO_2-DOUT") (pintype "output"))
    )
    (net (code "58") (name "unconnected-(U1-IO4-Pad26)") (class "Default")
      (node (ref "U1") (pin "26") (pinfunction "IO4_26") (pintype "bidirectional"))
    )
    (net (code "59") (name "unconnected-(U1-IO33-Pad9)") (class "Default")
      (node (ref "U1") (pin "9") (pinfunction "IO33_9") (pintype "bidirectional"))
    )
    (net (code "60") (name "unconnected-(U1-IO34-Pad6)") (class "Default")
      (node (ref "U1") (pin "6") (pinfunction "IO34_6") (pintype "input"))
    )
    (net (code "61") (name "unconnected-(U1-IO35-Pad7)") (class "Default")
      (node (ref "U1") (pin "7") (pinfunction "IO35_7") (pintype "input"))
    )
    (net (code "62") (name "unconnected-(U1-SCK{slash}CLK-Pad20)") (class "Default")
      (node (ref "U1") (pin "20") (pinfunction "SCK/CLK_20") (pintype "bidirectional"))
    )
    (net (code "63") (name "unconnected-(U1-SCS{slash}CMD-Pad19)") (class "Default")
      (node (ref "U1") (pin "19") (pinfunction "SCS/CMD_19") (pintype "bidirectional"))
    )
    (net (code "64") (name "unconnected-(U1-SENSOR_VN-Pad5)") (class "Default")
      (node (ref "U1") (pin "5") (pinfunction "SENSOR_VN_5") (pintype "input"))
    )
    (net (code "65") (name "unconnected-(U1-SENSOR_VP-Pad4)") (class "Default")
      (node (ref "U1") (pin "4") (pinfunction "SENSOR_VP_4") (pintype "input"))
    )
    (net (code "66") (name "unconnected-(U1-SHD{slash}SD2-Pad17)") (class "Default")
      (node (ref "U1") (pin "17") (pinfunction "SHD/SD2_17") (pintype "bidirectional"))
    )
    (net (code "67") (name "unconnected-(U1-SWP{slash}SD3-Pad18)") (class "Default")
      (node (ref "U1") (pin "18") (pinfunction "SWP/SD3_18") (pintype "bidirectional"))
    )
    (net (code "68") (name "unconnected-(U2-DRDY-Pad14)") (class "Default")
      (node (ref "U2") (pin "14") (pinfunction "DRDY_14") (pintype "passive"))
    )
    (net (code "69") (name "unconnected-(U2-INT2-Pad13)") (class "Default")
      (node (ref "U2") (pin "13") (pinfunction "INT2_13") (pintype "passive"))
    )
    (net (code "70") (name "unconnected-(U2-RESERVED-Pad7)") (class "Default")
      (node (ref "U2") (pin "7") (pinfunction "RESERVED_7") (pintype "passive"))
    )
    (net (code "71") (name "unconnected-(U4-CRS-Pad14)") (class "Default")
      (node (ref "U4") (pin "14") (pinfunction "CRS_14") (pintype "bidirectional"))
    )
    (net (code "72") (name "unconnected-(U4-NINT{slash}TXER{slash}TXD4-Pad18)") (class "Default")
      (node (ref "U4") (pin "18") (pinfunction "NINT/TXER/TXD4_18") (pintype "input"))
    )
    (net (code "73") (name "unconnected-(U4-RXDV-Pad26)") (class "Default")
      (node (ref "U4") (pin "26") (pinfunction "RXDV_26") (pintype "bidirectional"))
    )
    (net (code "74") (name "unconnected-(U4-TXCLK-Pad20)") (class "Default")
      (node (ref "U4") (pin "20") (pinfunction "TXCLK_20") (pintype "input"))
    )
    (net (code "75") (name "unconnected-(U4-XTAL2-Pad4)") (class "Default")
      (node (ref "U4") (pin "4") (pinfunction "XTAL2_4") (pintype "bidirectional"))
    )
  )
)
